# Sheet1.net
KiCad netlist of a schematic drawn in Altium Designer
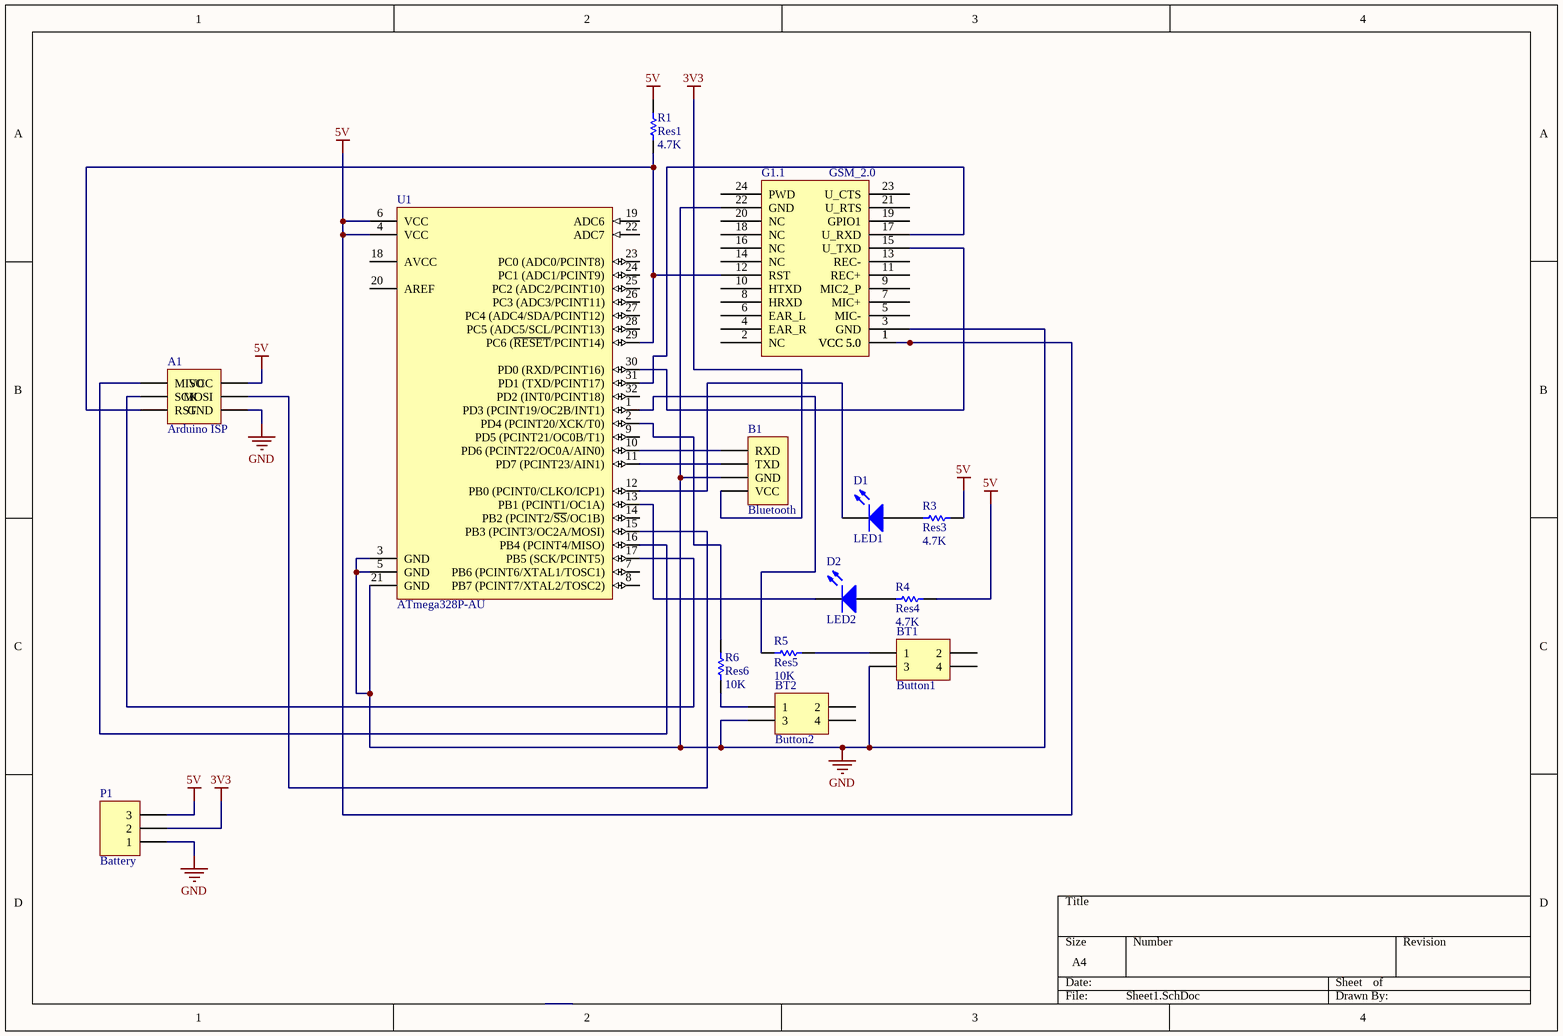
[diagram p0: Sheet1.SchDoc]

(export (version "E")
  (design (tool "Eeschema 10.0.6"))
  (components
    (comp (ref "A1")
      (value "Arduino ISP")
      (footprint "HDR2X3H")
      (description "Header, 3-Pin, Dual row, Right Angle")
      (fields (field (name "PUBLISHER") "Altium Limited"))
      (libsource (lib "Miscellaneous Connectors") (part "Header 3X2H"))
    )
    (comp (ref "B1")
      (value "Bluetooth")
      (footprint "HDR1X4")
      (description "Header, 4-Pin")
      (fields (field (name "PUBLISHER") "Altium Limited"))
      (libsource (lib "Miscellaneous Connectors") (part "Header 4"))
    )
    (comp (ref "BT1")
      (value "Button1")
      (footprint "HDR2X2")
      (description "Header, 2-Pin, Dual row")
      (fields (field (name "PUBLISHER") "Altium Limited"))
      (libsource (lib "Miscellaneous Connectors") (part "Header 2X2"))
    )
    (comp (ref "BT2")
      (value "Button2")
      (footprint "HDR2X2")
      (description "Header, 2-Pin, Dual row")
      (fields (field (name "PUBLISHER") "Altium Limited"))
      (libsource (lib "Miscellaneous Connectors") (part "Header 2X2"))
    )
    (comp (ref "D1")
      (value "LED1")
      (footprint "LED-0")
      (description "Typical INFRARED GaAs LED")
      (fields (field (name "PUBLISHER") "Altium Limited"))
      (libsource (lib "Miscellaneous Devices") (part "LED0"))
    )
    (comp (ref "D2")
      (value "LED2")
      (footprint "LED-0")
      (description "Typical INFRARED GaAs LED")
      (fields (field (name "PUBLISHER") "Altium Limited"))
      (libsource (lib "Miscellaneous Devices") (part "LED0"))
    )
    (comp (ref "G1.1") (value "GSM_2.0") (footprint "DIP24") (libsource (lib "GSM") (part "Component_1")))
    (comp (ref "P1")
      (value "Battery")
      (footprint "HDR1X3")
      (description "Header, 3-Pin")
      (fields (field (name "PUBLISHER") "Altium Limited"))
      (libsource (lib "Miscellaneous Connectors") (part "Header 3"))
    )
    (comp (ref "R1")
      (value "Res1")
      (footprint "AXIAL-0.3")
      (description "Resistor")
      (fields (field (name "ALTIUM_VALUE") "4.7K") (field (name "PUBLISHER") "Altium Limited"))
      (libsource (lib "Miscellaneous Devices") (part "Res1"))
    )
    (comp (ref "R3")
      (value "Res3")
      (footprint "AXIAL-0.3")
      (description "Resistor")
      (fields (field (name "ALTIUM_VALUE") "4.7K") (field (name "PUBLISHER") "Altium Limited"))
      (libsource (lib "Miscellaneous Devices") (part "Res1"))
    )
    (comp (ref "R4")
      (value "Res4")
      (footprint "AXIAL-0.3")
      (description "Resistor")
      (fields (field (name "ALTIUM_VALUE") "4.7K") (field (name "PUBLISHER") "Altium Limited"))
      (libsource (lib "Miscellaneous Devices") (part "Res1"))
    )
    (comp (ref "R5")
      (value "Res5")
      (footprint "AXIAL-0.3")
      (description "Resistor")
      (fields (field (name "ALTIUM_VALUE") "10K") (field (name "PUBLISHER") "Altium Limited"))
      (libsource (lib "Miscellaneous Devices") (part "Res1"))
    )
    (comp (ref "R6")
      (value "Res6")
      (footprint "AXIAL-0.3")
      (description "Resistor")
      (fields (field (name "ALTIUM_VALUE") "10K") (field (name "PUBLISHER") "Altium Limited"))
      (libsource (lib "Miscellaneous Devices") (part "Res1"))
    )
    (comp (ref "U1")
      (value "ATmega328P-AU")
      (footprint "32A_N")
      (fields (field (name "PUBLISHER") "Altium Limited"))
      (libsource (lib "Atmel Microcontroller 8-Bit megaAVR") (part "ATmega328P-AU"))
    )
  )
  (nets
    (net (code "1") (name "3V3") (class "Default")
      (node (ref "B1") (pin "4") (pinfunction "VCC_4") (pintype "passive"))
      (node (ref "P1") (pin "2") (pinfunction "2_2") (pintype "passive"))
    )
    (net (code "2") (name "5V") (class "Default")
      (node (ref "A1") (pin "2") (pinfunction "VCC_2") (pintype "passive"))
      (node (ref "G1.1") (pin "1") (pinfunction "VCC_5.0_1") (pintype "passive"))
      (node (ref "P1") (pin "3") (pinfunction "3_3") (pintype "passive"))
      (node (ref "R1") (pin "2") (pinfunction "2_2") (pintype "passive"))
      (node (ref "R3") (pin "1") (pinfunction "1_1") (pintype "passive"))
      (node (ref "R4") (pin "1") (pinfunction "1_1") (pintype "passive"))
      (node (ref "U1") (pin "4") (pinfunction "VCC_4") (pintype "power_in"))
      (node (ref "U1") (pin "6") (pinfunction "VCC_6") (pintype "power_in"))
    )
    (net (code "3") (name "GND") (class "Default")
      (node (ref "A1") (pin "6") (pinfunction "GND_6") (pintype "passive"))
      (node (ref "B1") (pin "3") (pinfunction "GND_3") (pintype "passive"))
      (node (ref "BT1") (pin "3") (pinfunction "3_3") (pintype "passive"))
      (node (ref "BT2") (pin "3") (pinfunction "3_3") (pintype "passive"))
      (node (ref "G1.1") (pin "22") (pinfunction "GND_22") (pintype "passive"))
      (node (ref "G1.1") (pin "3") (pinfunction "GND_3") (pintype "passive"))
      (node (ref "P1") (pin "1") (pinfunction "1_1") (pintype "passive"))
      (node (ref "U1") (pin "21") (pinfunction "GND_21") (pintype "power_in"))
      (node (ref "U1") (pin "3") (pinfunction "GND_3") (pintype "power_in"))
      (node (ref "U1") (pin "5") (pinfunction "GND_5") (pintype "power_in"))
    )
    (net (code "4") (name "Net-(A1-MISO)") (class "Default")
      (node (ref "A1") (pin "1") (pinfunction "MISO_1") (pintype "passive"))
      (node (ref "U1") (pin "16") (pinfunction "PB4_(PCINT4/MISO)_16") (pintype "bidirectional"))
    )
    (net (code "5") (name "Net-(A1-MOSI)") (class "Default")
      (node (ref "A1") (pin "4") (pinfunction "MOSI_4") (pintype "passive"))
      (node (ref "U1") (pin "15") (pinfunction "PB3_(PCINT3/OC2A/MOSI)_15") (pintype "bidirectional"))
    )
    (net (code "6") (name "Net-(A1-RST)") (class "Default")
      (node (ref "A1") (pin "5") (pinfunction "RST_5") (pintype "passive"))
      (node (ref "G1.1") (pin "12") (pinfunction "RST_12") (pintype "passive"))
      (node (ref "R1") (pin "1") (pinfunction "1_1") (pintype "passive"))
      (node (ref "U1") (pin "29") (pinfunction "PC6_(~{RESET}/PCINT14)_29") (pintype "bidirectional"))
    )
    (net (code "7") (name "Net-(A1-SCK)") (class "Default")
      (node (ref "A1") (pin "3") (pinfunction "SCK_3") (pintype "passive"))
      (node (ref "U1") (pin "17") (pinfunction "PB5_(SCK/PCINT5)_17") (pintype "bidirectional"))
    )
    (net (code "8") (name "Net-(B1-RXD)") (class "Default")
      (node (ref "B1") (pin "1") (pinfunction "RXD_1") (pintype "passive"))
      (node (ref "U1") (pin "10") (pinfunction "PD6_(PCINT22/OC0A/AIN0)_10") (pintype "bidirectional"))
    )
    (net (code "9") (name "Net-(B1-TXD)") (class "Default")
      (node (ref "B1") (pin "2") (pinfunction "TXD_2") (pintype "passive"))
      (node (ref "U1") (pin "11") (pinfunction "PD7_(PCINT23/AIN1)_11") (pintype "bidirectional"))
    )
    (net (code "10") (name "Net-(BT1-Pad1)") (class "Default")
      (node (ref "BT1") (pin "1") (pinfunction "1_1") (pintype "passive"))
      (node (ref "R5") (pin "1") (pinfunction "1_1") (pintype "passive"))
    )
    (net (code "11") (name "Net-(BT2-Pad1)") (class "Default")
      (node (ref "BT2") (pin "1") (pinfunction "1_1") (pintype "passive"))
      (node (ref "R6") (pin "1") (pinfunction "1_1") (pintype "passive"))
    )
    (net (code "12") (name "Net-(D1-A)") (class "Default")
      (node (ref "D1") (pin "1") (pinfunction "A_1") (pintype "passive"))
      (node (ref "R3") (pin "2") (pinfunction "2_2") (pintype "passive"))
    )
    (net (code "13") (name "Net-(D1-K)") (class "Default")
      (node (ref "D1") (pin "2") (pinfunction "K_2") (pintype "passive"))
      (node (ref "U1") (pin "12") (pinfunction "PB0_(PCINT0/CLKO/ICP1)_12") (pintype "bidirectional"))
    )
    (net (code "14") (name "Net-(D2-A)") (class "Default")
      (node (ref "D2") (pin "1") (pinfunction "A_1") (pintype "passive"))
      (node (ref "R4") (pin "2") (pinfunction "2_2") (pintype "passive"))
    )
    (net (code "15") (name "Net-(D2-K)") (class "Default")
      (node (ref "D2") (pin "2") (pinfunction "K_2") (pintype "passive"))
      (node (ref "U1") (pin "13") (pinfunction "PB1_(PCINT1/OC1A)_13") (pintype "bidirectional"))
    )
    (net (code "16") (name "Net-(G1.1-U_RXD)") (class "Default")
      (node (ref "G1.1") (pin "17") (pinfunction "U_RXD_17") (pintype "passive"))
      (node (ref "U1") (pin "31") (pinfunction "PD1_(TXD/PCINT17)_31") (pintype "bidirectional"))
    )
    (net (code "17") (name "Net-(G1.1-U_TXD)") (class "Default")
      (node (ref "G1.1") (pin "15") (pinfunction "U_TXD_15") (pintype "passive"))
      (node (ref "U1") (pin "30") (pinfunction "PD0_(RXD/PCINT16)_30") (pintype "bidirectional"))
    )
    (net (code "18") (name "Net-(U1-PD3_(PCINT19{slash}OC2B{slash}INT1))") (class "Default")
      (node (ref "R5") (pin "2") (pinfunction "2_2") (pintype "passive"))
      (node (ref "U1") (pin "1") (pinfunction "PD3_(PCINT19/OC2B/INT1)_1") (pintype "bidirectional"))
    )
    (net (code "19") (name "Net-(U1-PD4_(PCINT20{slash}XCK{slash}T0))") (class "Default")
      (node (ref "R6") (pin "2") (pinfunction "2_2") (pintype "passive"))
      (node (ref "U1") (pin "2") (pinfunction "PD4_(PCINT20/XCK/T0)_2") (pintype "bidirectional"))
    )
    (net (code "20") (name "unconnected-(BT1-Pad2)") (class "Default")
      (node (ref "BT1") (pin "2") (pinfunction "2_2") (pintype "passive"))
    )
    (net (code "21") (name "unconnected-(BT1-Pad4)") (class "Default")
      (node (ref "BT1") (pin "4") (pinfunction "4_4") (pintype "passive"))
    )
    (net (code "22") (name "unconnected-(BT2-Pad2)") (class "Default")
      (node (ref "BT2") (pin "2") (pinfunction "2_2") (pintype "passive"))
    )
    (net (code "23") (name "unconnected-(BT2-Pad4)") (class "Default")
      (node (ref "BT2") (pin "4") (pinfunction "4_4") (pintype "passive"))
    )
    (net (code "24") (name "unconnected-(G1.1-EAR_L-Pad6)") (class "Default")
      (node (ref "G1.1") (pin "6") (pinfunction "EAR_L_6") (pintype "passive"))
    )
    (net (code "25") (name "unconnected-(G1.1-EAR_R-Pad4)") (class "Default")
      (node (ref "G1.1") (pin "4") (pinfunction "EAR_R_4") (pintype "passive"))
    )
    (net (code "26") (name "unconnected-(G1.1-GPIO1-Pad19)") (class "Default")
      (node (ref "G1.1") (pin "19") (pinfunction "GPIO1_19") (pintype "passive"))
    )
    (net (code "27") (name "unconnected-(G1.1-HRXD-Pad8)") (class "Default")
      (node (ref "G1.1") (pin "8") (pinfunction "HRXD_8") (pintype "passive"))
    )
    (net (code "28") (name "unconnected-(G1.1-HTXD-Pad10)") (class "Default")
      (node (ref "G1.1") (pin "10") (pinfunction "HTXD_10") (pintype "passive"))
    )
    (net (code "29") (name "unconnected-(G1.1-MIC+-Pad7)") (class "Default")
      (node (ref "G1.1") (pin "7") (pinfunction "MIC+_7") (pintype "passive"))
    )
    (net (code "30") (name "unconnected-(G1.1-MIC--Pad5)") (class "Default")
      (node (ref "G1.1") (pin "5") (pinfunction "MIC-_5") (pintype "passive"))
    )
    (net (code "31") (name "unconnected-(G1.1-MIC2_P-Pad9)") (class "Default")
      (node (ref "G1.1") (pin "9") (pinfunction "MIC2_P_9") (pintype "passive"))
    )
    (net (code "32") (name "unconnected-(G1.1-NC-Pad2)") (class "Default")
      (node (ref "G1.1") (pin "2") (pinfunction "NC_2") (pintype "passive"))
    )
    (net (code "33") (name "unconnected-(G1.1-NC-Pad14)") (class "Default")
      (node (ref "G1.1") (pin "14") (pinfunction "NC_14") (pintype "passive"))
    )
    (net (code "34") (name "unconnected-(G1.1-NC-Pad16)") (class "Default")
      (node (ref "G1.1") (pin "16") (pinfunction "NC_16") (pintype "passive"))
    )
    (net (code "35") (name "unconnected-(G1.1-NC-Pad18)") (class "Default")
      (node (ref "G1.1") (pin "18") (pinfunction "NC_18") (pintype "passive"))
    )
    (net (code "36") (name "unconnected-(G1.1-NC-Pad20)") (class "Default")
      (node (ref "G1.1") (pin "20") (pinfunction "NC_20") (pintype "passive"))
    )
    (net (code "37") (name "unconnected-(G1.1-PWD-Pad24)") (class "Default")
      (node (ref "G1.1") (pin "24") (pinfunction "PWD_24") (pintype "passive"))
    )
    (net (code "38") (name "unconnected-(G1.1-REC+-Pad11)") (class "Default")
      (node (ref "G1.1") (pin "11") (pinfunction "REC+_11") (pintype "passive"))
    )
    (net (code "39") (name "unconnected-(G1.1-REC--Pad13)") (class "Default")
      (node (ref "G1.1") (pin "13") (pinfunction "REC-_13") (pintype "passive"))
    )
    (net (code "40") (name "unconnected-(G1.1-U_CTS-Pad23)") (class "Default")
      (node (ref "G1.1") (pin "23") (pinfunction "U_CTS_23") (pintype "passive"))
    )
    (net (code "41") (name "unconnected-(G1.1-U_RTS-Pad21)") (class "Default")
      (node (ref "G1.1") (pin "21") (pinfunction "U_RTS_21") (pintype "passive"))
    )
    (net (code "42") (name "unconnected-(U1-ADC6-Pad19)") (class "Default")
      (node (ref "U1") (pin "19") (pinfunction "ADC6_19") (pintype "input"))
    )
    (net (code "43") (name "unconnected-(U1-ADC7-Pad22)") (class "Default")
      (node (ref "U1") (pin "22") (pinfunction "ADC7_22") (pintype "input"))
    )
    (net (code "44") (name "unconnected-(U1-AREF-Pad20)") (class "Default")
      (node (ref "U1") (pin "20") (pinfunction "AREF_20") (pintype "passive"))
    )
    (net (code "45") (name "unconnected-(U1-AVCC-Pad18)") (class "Default")
      (node (ref "U1") (pin "18") (pinfunction "AVCC_18") (pintype "power_in"))
    )
    (net (code "46") (name "unconnected-(U1-PB2_(PCINT2{slash}~{SS}{slash}OC1B)-Pad14)") (class "Default")
      (node (ref "U1") (pin "14") (pinfunction "PB2_(PCINT2/~{SS}/OC1B)_14") (pintype "bidirectional"))
    )
    (net (code "47") (name "unconnected-(U1-PB6_(PCINT6{slash}XTAL1{slash}TOSC1)-Pad7)") (class "Default")
      (node (ref "U1") (pin "7") (pinfunction "PB6_(PCINT6/XTAL1/TOSC1)_7") (pintype "bidirectional"))
    )
    (net (code "48") (name "unconnected-(U1-PB7_(PCINT7{slash}XTAL2{slash}TOSC2)-Pad8)") (class "Default")
      (node (ref "U1") (pin "8") (pinfunction "PB7_(PCINT7/XTAL2/TOSC2)_8") (pintype "bidirectional"))
    )
    (net (code "49") (name "unconnected-(U1-PC0_(ADC0{slash}PCINT8)-Pad23)") (class "Default")
      (node (ref "U1") (pin "23") (pinfunction "PC0_(ADC0/PCINT8)_23") (pintype "bidirectional"))
    )
    (net (code "50") (name "unconnected-(U1-PC1_(ADC1{slash}PCINT9)-Pad24)") (class "Default")
      (node (ref "U1") (pin "24") (pinfunction "PC1_(ADC1/PCINT9)_24") (pintype "bidirectional"))
    )
    (net (code "51") (name "unconnected-(U1-PC2_(ADC2{slash}PCINT10)-Pad25)") (class "Default")
      (node (ref "U1") (pin "25") (pinfunction "PC2_(ADC2/PCINT10)_25") (pintype "bidirectional"))
    )
    (net (code "52") (name "unconnected-(U1-PC3_(ADC3{slash}PCINT11)-Pad26)") (class "Default")
      (node (ref "U1") (pin "26") (pinfunction "PC3_(ADC3/PCINT11)_26") (pintype "bidirectional"))
    )
    (net (code "53") (name "unconnected-(U1-PC4_(ADC4{slash}SDA{slash}PCINT12)-Pad27)") (class "Default")
      (node (ref "U1") (pin "27") (pinfunction "PC4_(ADC4/SDA/PCINT12)_27") (pintype "bidirectional"))
    )
    (net (code "54") (name "unconnected-(U1-PC5_(ADC5{slash}SCL{slash}PCINT13)-Pad28)") (class "Default")
      (node (ref "U1") (pin "28") (pinfunction "PC5_(ADC5/SCL/PCINT13)_28") (pintype "bidirectional"))
    )
    (net (code "55") (name "unconnected-(U1-PD2_(INT0{slash}PCINT18)-Pad32)") (class "Default")
      (node (ref "U1") (pin "32") (pinfunction "PD2_(INT0/PCINT18)_32") (pintype "bidirectional"))
    )
    (net (code "56") (name "unconnected-(U1-PD5_(PCINT21{slash}OC0B{slash}T1)-Pad9)") (class "Default")
      (node (ref "U1") (pin "9") (pinfunction "PD5_(PCINT21/OC0B/T1)_9") (pintype "bidirectional"))
    )
  )
)
